# DMGC-PWR-01_2-3.net
KiCad netlist of a schematic drawn in EAGLE
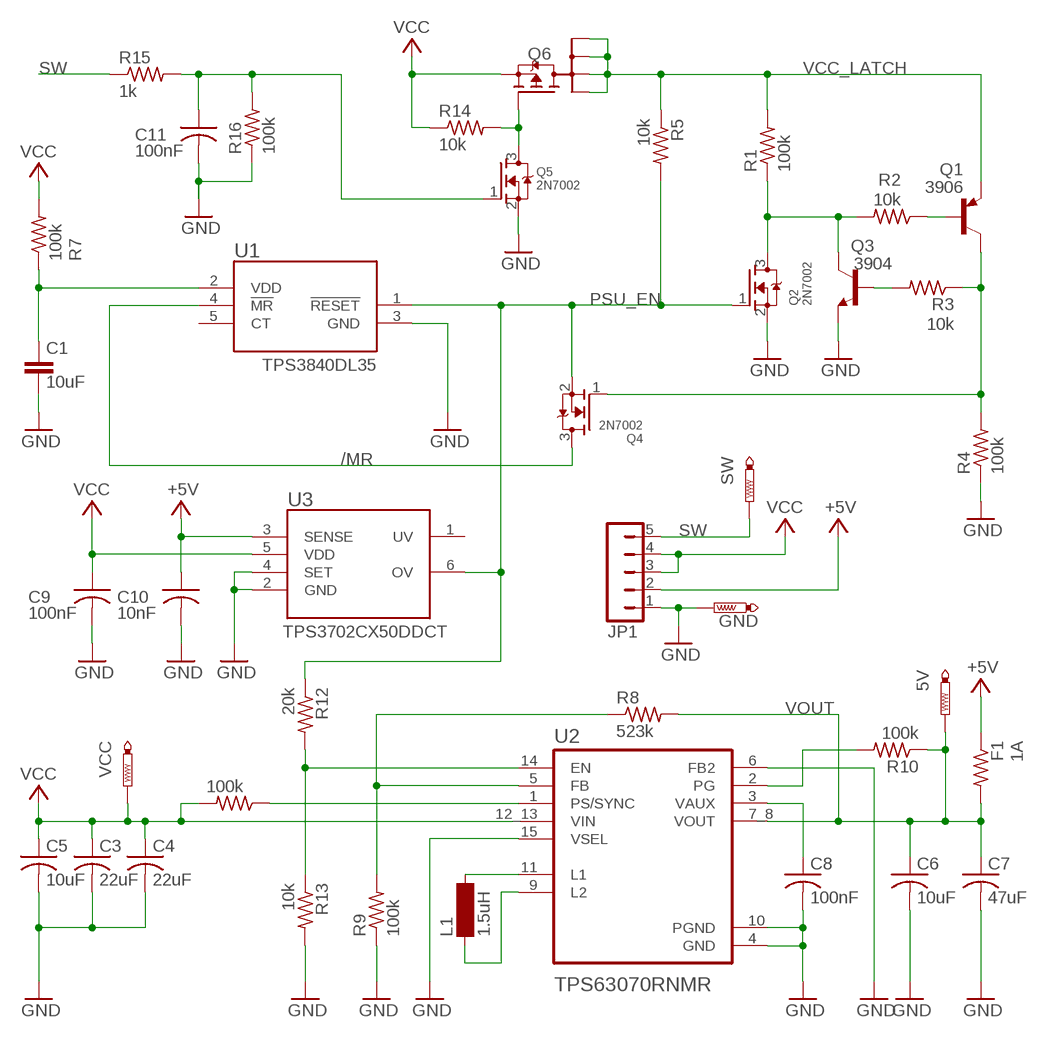
[diagram p0: schematic, sheet 1]

(export (version "E")
  (design (tool "Eeschema 10.0.6"))
  (components
    (comp (ref "5V")
      (value "PTR1B1,27")
      (footprint "eagle-import:B1,27")
      (libsource (lib "eagle-import") (part "PTR1B1,27"))
    )
    (comp (ref "C1")
      (value "10uF")
      (footprint "eagle-import:C0603")
      (libsource (lib "eagle-import") (part "C-EUC0603"))
    )
    (comp (ref "C3")
      (value "22uF")
      (footprint "eagle-import:C1206")
      (libsource (lib "eagle-import") (part "C-USC1206"))
    )
    (comp (ref "C4")
      (value "22uF")
      (footprint "eagle-import:C1206")
      (libsource (lib "eagle-import") (part "C-USC1206"))
    )
    (comp (ref "C5")
      (value "10uF")
      (footprint "eagle-import:C0603")
      (libsource (lib "eagle-import") (part "C-USC0603"))
    )
    (comp (ref "C6")
      (value "10uF")
      (footprint "eagle-import:C0603")
      (libsource (lib "eagle-import") (part "C-USC0603"))
    )
    (comp (ref "C7")
      (value "47uF")
      (footprint "eagle-import:C1206")
      (libsource (lib "eagle-import") (part "C-USC1206"))
    )
    (comp (ref "C8")
      (value "100nF")
      (footprint "eagle-import:C0603")
      (libsource (lib "eagle-import") (part "C-USC0603"))
    )
    (comp (ref "C9")
      (value "100nF")
      (footprint "eagle-import:C0603")
      (libsource (lib "eagle-import") (part "C-USC0603"))
    )
    (comp (ref "C10")
      (value "10nF")
      (footprint "eagle-import:C0603")
      (libsource (lib "eagle-import") (part "C-USC0603"))
    )
    (comp (ref "C11")
      (value "100nF")
      (footprint "eagle-import:C0603")
      (libsource (lib "eagle-import") (part "C-USC0603"))
    )
    (comp (ref "F1")
      (value "1A")
      (footprint "eagle-import:R0603")
      (libsource (lib "eagle-import") (part "R-US_R0603"))
    )
    (comp (ref "GND")
      (value "PTR1B1,27")
      (footprint "eagle-import:B1,27")
      (libsource (lib "eagle-import") (part "PTR1B1,27"))
    )
    (comp (ref "JP1")
      (value "JP5")
      (footprint "eagle-import:JP5")
      (libsource (lib "eagle-import") (part "JP5"))
    )
    (comp (ref "L1")
      (value "1.5uH")
      (footprint "eagle-import:1212")
      (libsource (lib "eagle-import") (part "LQH3NPN2R2"))
    )
    (comp (ref "Q1")
      (value "MMBT3906LT1SMD")
      (footprint "eagle-import:SOT23-BEC")
      (libsource (lib "eagle-import") (part "MMBT3906SMDLT1"))
    )
    (comp (ref "Q2")
      (value "2N7002")
      (footprint "eagle-import:SOT23")
      (libsource (lib "eagle-import") (part "MOSFET-NREFLOW"))
    )
    (comp (ref "Q3")
      (value "3904")
      (footprint "eagle-import:SOT23-BEC")
      (libsource (lib "eagle-import") (part "-NPN-SOT23-BECMMBT3904LT1"))
    )
    (comp (ref "Q4")
      (value "2N7002")
      (footprint "eagle-import:SOT23")
      (libsource (lib "eagle-import") (part "MOSFET-NREFLOW"))
    )
    (comp (ref "Q5")
      (value "2N7002")
      (footprint "eagle-import:SOT23")
      (libsource (lib "eagle-import") (part "MOSFET-NREFLOW"))
    )
    (comp (ref "Q6")
      (value "SI1401EDH")
      (footprint "eagle-import:SOT363_INFINEON")
      (libsource (lib "eagle-import") (part "SI1401EDH"))
    )
    (comp (ref "R1")
      (value "100k")
      (footprint "eagle-import:R0603")
      (libsource (lib "eagle-import") (part "R-US_R0603"))
    )
    (comp (ref "R2")
      (value "10k")
      (footprint "eagle-import:R0603")
      (libsource (lib "eagle-import") (part "R-US_R0603"))
    )
    (comp (ref "R3")
      (value "10k")
      (footprint "eagle-import:R0603")
      (libsource (lib "eagle-import") (part "R-US_R0603"))
    )
    (comp (ref "R4")
      (value "100k")
      (footprint "eagle-import:R0603")
      (libsource (lib "eagle-import") (part "R-US_R0603"))
    )
    (comp (ref "R5")
      (value "10k")
      (footprint "eagle-import:R0603")
      (libsource (lib "eagle-import") (part "R-US_R0603"))
    )
    (comp (ref "R7")
      (value "100k")
      (footprint "eagle-import:R0603")
      (libsource (lib "eagle-import") (part "R-US_R0603"))
    )
    (comp (ref "R8")
      (value "523k")
      (footprint "eagle-import:R0603")
      (libsource (lib "eagle-import") (part "R-US_R0603"))
    )
    (comp (ref "R9")
      (value "100k")
      (footprint "eagle-import:R0603")
      (libsource (lib "eagle-import") (part "R-US_R0603"))
    )
    (comp (ref "R10")
      (value "100k")
      (footprint "eagle-import:R0603")
      (libsource (lib "eagle-import") (part "R-US_R0603"))
    )
    (comp (ref "R11")
      (value "100k")
      (footprint "eagle-import:R0603")
      (libsource (lib "eagle-import") (part "R-US_R0603"))
    )
    (comp (ref "R12")
      (value "20k")
      (footprint "eagle-import:R0603")
      (libsource (lib "eagle-import") (part "R-US_R0603"))
    )
    (comp (ref "R13")
      (value "10k")
      (footprint "eagle-import:R0603")
      (libsource (lib "eagle-import") (part "R-US_R0603"))
    )
    (comp (ref "R14")
      (value "10k")
      (footprint "eagle-import:R0603")
      (libsource (lib "eagle-import") (part "R-US_R0603"))
    )
    (comp (ref "R15")
      (value "1k")
      (footprint "eagle-import:R0603")
      (libsource (lib "eagle-import") (part "R-US_R0603"))
    )
    (comp (ref "R16")
      (value "100k")
      (footprint "eagle-import:R0603")
      (libsource (lib "eagle-import") (part "R-US_R0603"))
    )
    (comp (ref "SW")
      (value "PTR1B1,27")
      (footprint "eagle-import:B1,27")
      (libsource (lib "eagle-import") (part "PTR1B1,27"))
    )
    (comp (ref "U1")
      (value "TPS3840")
      (footprint "eagle-import:SOT-23-5")
      (libsource (lib "eagle-import") (part "TPS3840"))
    )
    (comp (ref "U2")
      (value "TPS63070RNMR")
      (footprint "eagle-import:VREG_TPS63070RNMR")
      (fields (field (name "MF") "Texas Instruments"))
      (libsource (lib "eagle-import") (part "TPS63070RNMR"))
    )
    (comp (ref "U3")
      (value "TPS3702")
      (footprint "eagle-import:SOT-23-6")
      (libsource (lib "eagle-import") (part "TPS3702"))
    )
    (comp (ref "VCC")
      (value "PTR1B1,27")
      (footprint "eagle-import:B1,27")
      (libsource (lib "eagle-import") (part "PTR1B1,27"))
    )
  )
  (nets
    (net (code "1") (name "+5V") (class "Default")
      (node (ref "C10") (pin "1") (pinfunction "1_1") (pintype "passive"))
      (node (ref "F1") (pin "1") (pinfunction "1_1") (pintype "passive"))
      (node (ref "JP1") (pin "2") (pinfunction "2_2") (pintype "passive"))
      (node (ref "U3") (pin "3") (pinfunction "SENSE_3") (pintype "input"))
    )
    (net (code "2") (name "/PSU_EN") (class "Default")
      (node (ref "Q2") (pin "1") (pinfunction "G_1") (pintype "bidirectional"))
      (node (ref "Q4") (pin "2") (pinfunction "S_2") (pintype "bidirectional"))
      (node (ref "R12") (pin "1") (pinfunction "1_1") (pintype "passive"))
      (node (ref "R5") (pin "2") (pinfunction "2_2") (pintype "passive"))
      (node (ref "U1") (pin "1") (pinfunction "~{RESET}_1") (pintype "output"))
      (node (ref "U3") (pin "6") (pinfunction "OV_6") (pintype "output"))
    )
    (net (code "3") (name "/SW") (class "Default")
      (node (ref "JP1") (pin "5") (pinfunction "5_5") (pintype "passive"))
      (node (ref "R15") (pin "1") (pinfunction "1_1") (pintype "passive"))
      (node (ref "SW") (pin "TP") (pinfunction "TP_TP") (pintype "input"))
    )
    (net (code "4") (name "/VCC_LATCH") (class "Default")
      (node (ref "Q1") (pin "E") (pinfunction "E_E") (pintype "passive"))
      (node (ref "Q6") (pin "1") (pinfunction "D1_1") (pintype "passive"))
      (node (ref "Q6") (pin "2") (pinfunction "D2_2") (pintype "passive"))
      (node (ref "Q6") (pin "5") (pinfunction "D5_5") (pintype "passive"))
      (node (ref "Q6") (pin "6") (pinfunction "D6_6") (pintype "passive"))
      (node (ref "R1") (pin "2") (pinfunction "2_2") (pintype "passive"))
      (node (ref "R5") (pin "1") (pinfunction "1_1") (pintype "passive"))
    )
    (net (code "5") (name "/VOUT") (class "Default")
      (node (ref "5V") (pin "TP") (pinfunction "TP_TP") (pintype "input"))
      (node (ref "C6") (pin "1") (pinfunction "1_1") (pintype "passive"))
      (node (ref "C7") (pin "1") (pinfunction "1_1") (pintype "passive"))
      (node (ref "F1") (pin "2") (pinfunction "2_2") (pintype "passive"))
      (node (ref "R10") (pin "1") (pinfunction "1_1") (pintype "passive"))
      (node (ref "R8") (pin "2") (pinfunction "2_2") (pintype "passive"))
      (node (ref "U2") (pin "7_8") (pinfunction "VOUT_7_8") (pintype "output"))
    )
    (net (code "6") (name "/{slash}MR") (class "Default")
      (node (ref "Q4") (pin "3") (pinfunction "D_3") (pintype "bidirectional"))
      (node (ref "U1") (pin "4") (pinfunction "~{MR}_4") (pintype "input"))
    )
    (net (code "7") (name "GND") (class "Default")
      (node (ref "C1") (pin "2") (pinfunction "2_2") (pintype "passive"))
      (node (ref "C10") (pin "2") (pinfunction "2_2") (pintype "passive"))
      (node (ref "C11") (pin "2") (pinfunction "2_2") (pintype "passive"))
      (node (ref "C3") (pin "2") (pinfunction "2_2") (pintype "passive"))
      (node (ref "C4") (pin "2") (pinfunction "2_2") (pintype "passive"))
      (node (ref "C5") (pin "2") (pinfunction "2_2") (pintype "passive"))
      (node (ref "C6") (pin "2") (pinfunction "2_2") (pintype "passive"))
      (node (ref "C7") (pin "2") (pinfunction "2_2") (pintype "passive"))
      (node (ref "C8") (pin "2") (pinfunction "2_2") (pintype "passive"))
      (node (ref "C9") (pin "2") (pinfunction "2_2") (pintype "passive"))
      (node (ref "GND") (pin "TP") (pinfunction "TP_TP") (pintype "input"))
      (node (ref "JP1") (pin "1") (pinfunction "1_1") (pintype "passive"))
      (node (ref "Q2") (pin "2") (pinfunction "S_2") (pintype "bidirectional"))
      (node (ref "Q3") (pin "E") (pinfunction "E_E") (pintype "passive"))
      (node (ref "Q5") (pin "2") (pinfunction "S_2") (pintype "bidirectional"))
      (node (ref "R13") (pin "2") (pinfunction "2_2") (pintype "passive"))
      (node (ref "R16") (pin "1") (pinfunction "1_1") (pintype "passive"))
      (node (ref "R4") (pin "1") (pinfunction "1_1") (pintype "passive"))
      (node (ref "R9") (pin "1") (pinfunction "1_1") (pintype "passive"))
      (node (ref "U1") (pin "3") (pinfunction "GND_3") (pintype "power_in"))
      (node (ref "U2") (pin "10") (pinfunction "PGND_10") (pintype "power_in"))
      (node (ref "U2") (pin "15") (pinfunction "VSEL_15") (pintype "input"))
      (node (ref "U2") (pin "4") (pinfunction "GND_4") (pintype "power_in"))
      (node (ref "U2") (pin "6") (pinfunction "FB2_6") (pintype "output"))
      (node (ref "U3") (pin "2") (pinfunction "GND_2") (pintype "power_in"))
      (node (ref "U3") (pin "4") (pinfunction "SET_4") (pintype "input"))
    )
    (net (code "8") (name "Net-(Q1-PadB)") (class "Default")
      (node (ref "Q1") (pin "B") (pinfunction "B_B") (pintype "passive"))
      (node (ref "R2") (pin "1") (pinfunction "1_1") (pintype "passive"))
    )
    (net (code "9") (name "Net-(Q2-D)") (class "Default")
      (node (ref "Q2") (pin "3") (pinfunction "D_3") (pintype "bidirectional"))
      (node (ref "Q3") (pin "C") (pinfunction "C_C") (pintype "passive"))
      (node (ref "R1") (pin "1") (pinfunction "1_1") (pintype "passive"))
      (node (ref "R2") (pin "2") (pinfunction "2_2") (pintype "passive"))
    )
    (net (code "10") (name "Net-(Q3-PadB)") (class "Default")
      (node (ref "Q3") (pin "B") (pinfunction "B_B") (pintype "passive"))
      (node (ref "R3") (pin "2") (pinfunction "2_2") (pintype "passive"))
    )
    (net (code "11") (name "Net-(Q4-G)") (class "Default")
      (node (ref "Q1") (pin "C") (pinfunction "C_C") (pintype "passive"))
      (node (ref "Q4") (pin "1") (pinfunction "G_1") (pintype "bidirectional"))
      (node (ref "R3") (pin "1") (pinfunction "1_1") (pintype "passive"))
      (node (ref "R4") (pin "2") (pinfunction "2_2") (pintype "passive"))
    )
    (net (code "12") (name "Net-(Q5-D)") (class "Default")
      (node (ref "Q5") (pin "3") (pinfunction "D_3") (pintype "bidirectional"))
      (node (ref "Q6") (pin "3") (pinfunction "G_3") (pintype "passive"))
      (node (ref "R14") (pin "2") (pinfunction "2_2") (pintype "passive"))
    )
    (net (code "13") (name "Net-(Q5-G)") (class "Default")
      (node (ref "C11") (pin "1") (pinfunction "1_1") (pintype "passive"))
      (node (ref "Q5") (pin "1") (pinfunction "G_1") (pintype "bidirectional"))
      (node (ref "R15") (pin "2") (pinfunction "2_2") (pintype "passive"))
      (node (ref "R16") (pin "2") (pinfunction "2_2") (pintype "passive"))
    )
    (net (code "14") (name "Net-(U1-VDD)") (class "Default")
      (node (ref "C1") (pin "1") (pinfunction "1_1") (pintype "passive"))
      (node (ref "R7") (pin "1") (pinfunction "1_1") (pintype "passive"))
      (node (ref "U1") (pin "2") (pinfunction "VDD_2") (pintype "power_in"))
    )
    (net (code "15") (name "Net-(U2-EN)") (class "Default")
      (node (ref "R12") (pin "2") (pinfunction "2_2") (pintype "passive"))
      (node (ref "R13") (pin "1") (pinfunction "1_1") (pintype "passive"))
      (node (ref "U2") (pin "14") (pinfunction "EN_14") (pintype "input"))
    )
    (net (code "16") (name "Net-(U2-FB)") (class "Default")
      (node (ref "R8") (pin "1") (pinfunction "1_1") (pintype "passive"))
      (node (ref "R9") (pin "2") (pinfunction "2_2") (pintype "passive"))
      (node (ref "U2") (pin "5") (pinfunction "FB_5") (pintype "input"))
    )
    (net (code "17") (name "Net-(U2-L1)") (class "Default")
      (node (ref "L1") (pin "2") (pinfunction "2_2") (pintype "passive"))
      (node (ref "U2") (pin "11") (pinfunction "L1_11") (pintype "bidirectional"))
    )
    (net (code "18") (name "Net-(U2-L2)") (class "Default")
      (node (ref "L1") (pin "1") (pinfunction "1_1") (pintype "passive"))
      (node (ref "U2") (pin "9") (pinfunction "L2_9") (pintype "bidirectional"))
    )
    (net (code "19") (name "Net-(U2-PG)") (class "Default")
      (node (ref "R10") (pin "2") (pinfunction "2_2") (pintype "passive"))
      (node (ref "U2") (pin "2") (pinfunction "PG_2") (pintype "output"))
    )
    (net (code "20") (name "Net-(U2-PS{slash}SYNC)") (class "Default")
      (node (ref "R11") (pin "1") (pinfunction "1_1") (pintype "passive"))
      (node (ref "U2") (pin "1") (pinfunction "PS/SYNC_1") (pintype "input"))
    )
    (net (code "21") (name "Net-(U2-VAUX)") (class "Default")
      (node (ref "C8") (pin "1") (pinfunction "1_1") (pintype "passive"))
      (node (ref "U2") (pin "3") (pinfunction "VAUX_3") (pintype "output"))
    )
    (net (code "22") (name "VCC") (class "Default")
      (node (ref "C3") (pin "1") (pinfunction "1_1") (pintype "passive"))
      (node (ref "C4") (pin "1") (pinfunction "1_1") (pintype "passive"))
      (node (ref "C5") (pin "1") (pinfunction "1_1") (pintype "passive"))
      (node (ref "C9") (pin "1") (pinfunction "1_1") (pintype "passive"))
      (node (ref "JP1") (pin "3") (pinfunction "3_3") (pintype "passive"))
      (node (ref "JP1") (pin "4") (pinfunction "4_4") (pintype "passive"))
      (node (ref "Q6") (pin "4") (pinfunction "S_4") (pintype "passive"))
      (node (ref "R11") (pin "2") (pinfunction "2_2") (pintype "passive"))
      (node (ref "R14") (pin "1") (pinfunction "1_1") (pintype "passive"))
      (node (ref "R7") (pin "2") (pinfunction "2_2") (pintype "passive"))
      (node (ref "U2") (pin "12_13") (pinfunction "VIN_12_13") (pintype "input"))
      (node (ref "U3") (pin "5") (pinfunction "VDD_5") (pintype "power_in"))
      (node (ref "VCC") (pin "TP") (pinfunction "TP_TP") (pintype "input"))
    )
    (net (code "23") (name "unconnected-(U1-CT-Pad5)") (class "Default")
      (node (ref "U1") (pin "5") (pinfunction "CT_5") (pintype "bidirectional"))
    )
    (net (code "24") (name "unconnected-(U3-UV-Pad1)") (class "Default")
      (node (ref "U3") (pin "1") (pinfunction "UV_1") (pintype "output"))
    )
  )
)
